# 1_MCU.net
KiCad netlist of a schematic drawn in Altium Designer
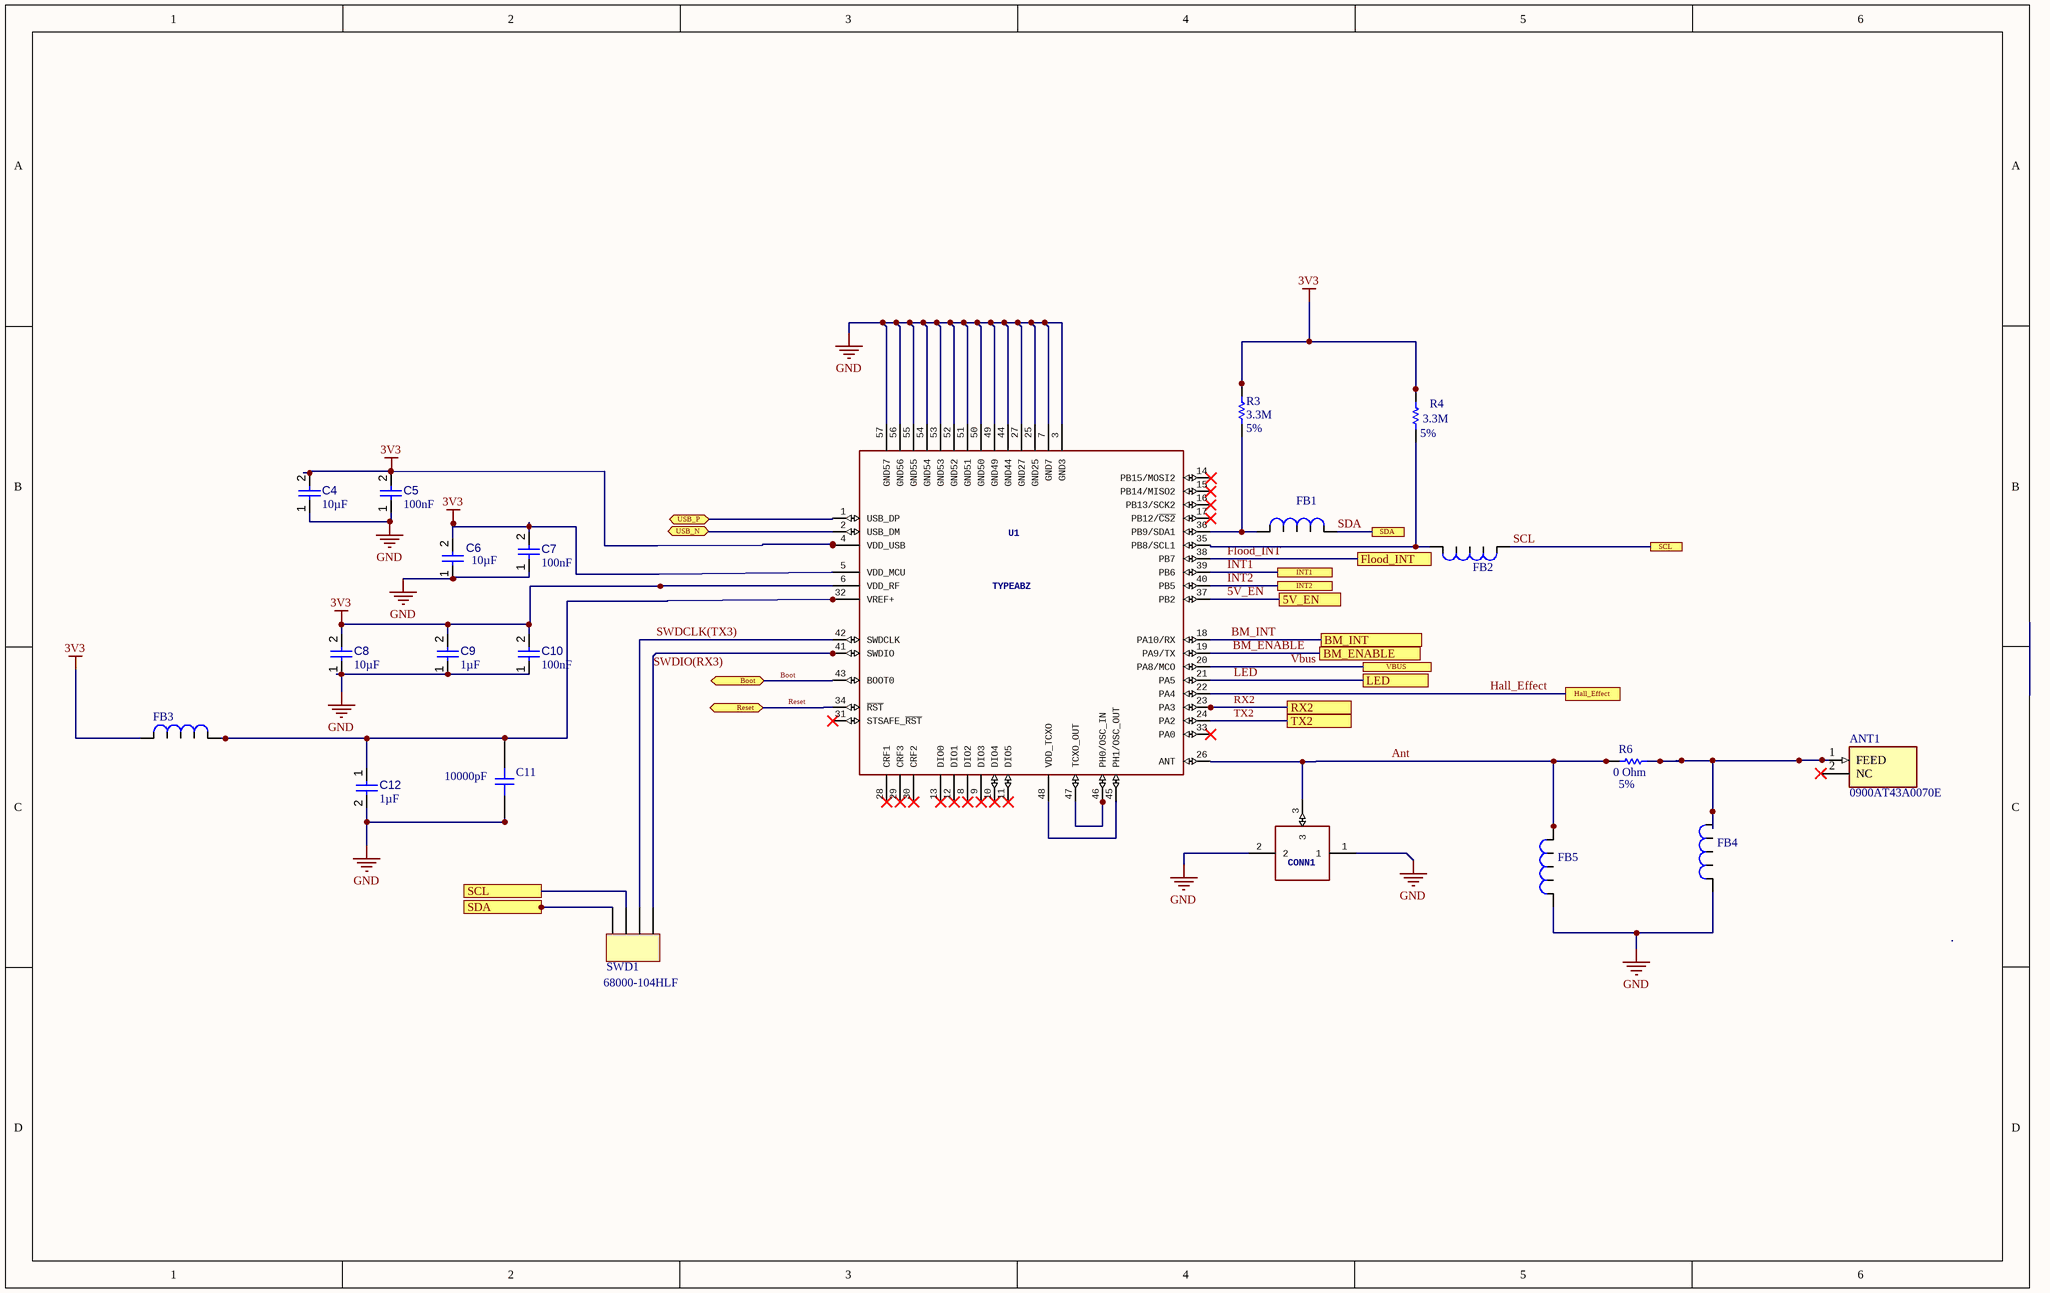
[diagram p0: [1]MCU.SchDoc]

(export (version "E")
  (design (tool "Eeschema 10.0.6"))
  (components
    (comp (ref "ANT1")
      (value "0900AT43A0070E")
      (footprint "SamacSys:ANTC7020X90N")
      (description "Antenna")
      (libsource (lib "Schlib_For_High_Voltage_Sensor") (part "0900AT43A0070E"))
    )
    (comp (ref "C4")
      (value "10µF")
      (footprint "CAPC0603(1608)100_L")
      (description "Chip Capacitor, 10µF +/-20%, 10V, 0603, Thickness 1 mm")
      (fields (field (name "TOLERANCE") "10%") (field (name "Comment") "Capacitor 10µF +/-20% 10V 0603"))
      (libsource (lib "Latium Technologies") (part "CAP-NP-2"))
    )
    (comp (ref "C5")
      (value "100nF")
      (footprint "CAPC1608X90X40ML10T20")
      (description "Chip Capacitor, 100 nF, +/- 10%, 50 V, 0603 (1608 Metric)")
      (fields (field (name "TOLERANCE") "10%") (field (name "Comment") "Capacitor 100 nF +/-10% 50 V 0603"))
      (libsource (lib "Latium Technologies") (part "CAP-NP-2"))
    )
    (comp (ref "C6")
      (value "10µF")
      (footprint "CAPC0603(1608)100_L")
      (description "Chip Capacitor, 10µF +/-20%, 10V, 0603, Thickness 1 mm")
      (fields (field (name "TOLERANCE") "10%") (field (name "Comment") "Capacitor 10µF +/-20% 10V 0603"))
      (libsource (lib "Latium Technologies") (part "CAP-NP-2"))
    )
    (comp (ref "C7")
      (value "100nF")
      (footprint "CAPC1608X90X40ML10T20")
      (description "Chip Capacitor, 100 nF, +/- 10%, 50 V, 0603 (1608 Metric)")
      (fields (field (name "TOLERANCE") "10%") (field (name "Comment") "Capacitor 100 nF +/-10% 50 V 0603"))
      (libsource (lib "Latium Technologies") (part "CAP-NP-2"))
    )
    (comp (ref "C8")
      (value "10µF")
      (footprint "CAPC0603(1608)100_L")
      (description "Chip Capacitor, 10µF +/-20%, 10V, 0603, Thickness 1 mm")
      (fields (field (name "TOLERANCE") "10%") (field (name "Comment") "Capacitor 10µF +/-20% 10V 0603"))
      (libsource (lib "Latium Technologies") (part "CAP-NP-2"))
    )
    (comp (ref "C9")
      (value "1µF")
      (footprint "CAPC1608X90X40ML10T20")
      (description "Chip Capacitor, 1 uF, +/- 10%, 25 V, 0603 (1608 Metric)")
      (fields (field (name "TOLERANCE") "10%") (field (name "Comment") "Capacitor 1 uF +/- 10% 25 V 0603"))
      (libsource (lib "Latium Technologies") (part "CAP-NP-2"))
    )
    (comp (ref "C10")
      (value "100nF")
      (footprint "CAPC1608X90X40ML10T20")
      (description "Chip Capacitor, 100 nF, +/- 10%, 50 V, 0603 (1608 Metric)")
      (fields (field (name "TOLERANCE") "10%") (field (name "Comment") "Capacitor 100 nF +/-10% 50 V 0603"))
      (libsource (lib "Latium Technologies") (part "CAP-NP-2"))
    )
    (comp (ref "C11")
      (value "10000PF")
      (footprint "CAPC0603")
      (description "CAP CER 10000PF 50V X7R 0603")
      (fields
        (field (name "MANUFACTURER") "Murata Electronics North America")
        (field (name "MANUFACTURER PART NUMBER") "GRM188R71H103KA01D")
        (field (name "CAPACITANCE") "10000pF")
      )
      (libsource (lib "Schlib_For_High_Voltage_Sensor") (part "GRM188R71H103KA01D"))
    )
    (comp (ref "C12")
      (value "1µF")
      (footprint "CAPC1608X90X40ML10T20")
      (description "Chip Capacitor, 1 uF, +/- 10%, 25 V, 0603 (1608 Metric)")
      (fields (field (name "TOLERANCE") "10%") (field (name "Comment") "Capacitor 1 uF +/- 10% 25 V 0603"))
      (libsource (lib "Latium Technologies") (part "CAP-NP-2"))
    )
    (comp (ref "CONN1")
      (value "U.FL-R-SMT-1")
      (footprint "U.FL-R-SMT-1")
      (fields (field (name "LIBRARYNAME") "Kris"))
      (libsource (lib "Schlib_For_High_Voltage_Sensor") (part "U.FL-R-SMT-1"))
    )
    (comp (ref "FB1")
      (value "BLM18AG102SN1D")
      (footprint "Ferrite Bead")
      (description "Ferrite Bead 1KOhm @100MHz")
      (libsource (lib "") (part "Ferrite Bead_1"))
    )
    (comp (ref "FB2")
      (value "BLM18AG102SN1D")
      (footprint "Ferrite Bead")
      (description "Ferrite Bead 1KOhm @100MHz")
      (libsource (lib "MasterLib") (part "Ferrite Bead"))
    )
    (comp (ref "FB3")
      (value "BLM18AG102SN1D")
      (footprint "Ferrite Bead")
      (description "Ferrite Bead 1KOhm @100MHz")
      (libsource (lib "MasterLib") (part "Ferrite Bead"))
    )
    (comp (ref "FB4")
      (value "BLM18AG102SN1D")
      (footprint "Ferrite Bead")
      (description "Ferrite Bead 1KOhm @100MHz")
      (libsource (lib "MasterLib") (part "Ferrite Bead"))
    )
    (comp (ref "FB5")
      (value "BLM18AG102SN1D")
      (footprint "Ferrite Bead")
      (description "Ferrite Bead 1KOhm @100MHz")
      (libsource (lib "MasterLib") (part "Ferrite Bead"))
    )
    (comp (ref "R3")
      (value "3.3M")
      (footprint "RES 0603")
      (description "RES 3.3M 5% 0.1W [0603]")
      (fields (field (name "TOLERANCE") "5%"))
      (libsource (lib "MasterLib") (part "RES 3.3M 1% 0.1W [0603]"))
    )
    (comp (ref "R4")
      (value "3.3M")
      (footprint "RES 0603")
      (description "RES 3.3M 5% 0.1W [0603]")
      (fields (field (name "TOLERANCE") "5%"))
      (libsource (lib "MasterLib") (part "RES 3.3M 1% 0.1W [0603]"))
    )
    (comp (ref "R6")
      (value "0 Ohm")
      (footprint "RES 0603")
      (description "RES 0 Ohm 5% 0.1W [0603]")
      (fields (field (name "TOLERANCE") "5%"))
      (libsource (lib "MasterLib") (part "RES 0 Ohm [0603]"))
    )
    (comp (ref "SWD1")
      (value "68000-104HLF")
      (footprint "4POS_HEADER")
      (description "4 Positions Header, Unshrouded Connector 0.100\" (2.54mm) Through Hole Gold or Gold, GXT™")
      (libsource (lib "OTX_Lib_Charger") (part "68000-104HLF"))
    )
    (comp (ref "U1")
      (value "TYPEABZ")
      (footprint "CMWX1ZZABZ")
      (description "CMWX1ZZABZ-078")
      (libsource (lib "Schlib_For_High_Voltage_Sensor") (part "TYPEABZ"))
    )
  )
  (nets
    (net (code "1") (name "/5V_EN") (class "Default")
      (node (ref "U1") (pin "37") (pinfunction "PB2_37") (pintype "bidirectional"))
    )
    (net (code "3") (name "/Ant") (class "Default")
      (node (ref "CONN1") (pin "3") (pinfunction "3_3") (pintype "bidirectional"))
      (node (ref "FB5") (pin "1") (pinfunction "1_1") (pintype "passive"))
      (node (ref "R6") (pin "1") (pinfunction "1_1") (pintype "passive"))
      (node (ref "U1") (pin "26") (pinfunction "ANT_26") (pintype "bidirectional"))
    )
    (net (code "4") (name "/BM_ENABLE") (class "Default")
      (node (ref "U1") (pin "19") (pinfunction "PA9/TX_19") (pintype "bidirectional"))
    )
    (net (code "5") (name "/BM_INT") (class "Default")
      (node (ref "U1") (pin "18") (pinfunction "PA10/RX_18") (pintype "bidirectional"))
    )
    (net (code "6") (name "/Boot") (class "Default")
      (node (ref "U1") (pin "43") (pinfunction "BOOT0_43") (pintype "bidirectional"))
    )
    (net (code "7") (name "/Flood_INT") (class "Default")
      (node (ref "U1") (pin "38") (pinfunction "PB7_38") (pintype "bidirectional"))
    )
    (net (code "8") (name "/Hall_Effect") (class "Default")
      (node (ref "U1") (pin "22") (pinfunction "PA4_22") (pintype "bidirectional"))
    )
    (net (code "9") (name "/INT1") (class "Default")
      (node (ref "U1") (pin "39") (pinfunction "PB6_39") (pintype "bidirectional"))
    )
    (net (code "10") (name "/INT2") (class "Default")
      (node (ref "U1") (pin "40") (pinfunction "PB5_40") (pintype "bidirectional"))
    )
    (net (code "11") (name "/LED") (class "Default")
      (node (ref "U1") (pin "21") (pinfunction "PA5_21") (pintype "bidirectional"))
    )
    (net (code "12") (name "/RX2") (class "Default")
      (node (ref "U1") (pin "23") (pinfunction "PA3_23") (pintype "bidirectional"))
    )
    (net (code "13") (name "/Reset") (class "Default")
      (node (ref "U1") (pin "34") (pinfunction "~{RST}_34") (pintype "bidirectional"))
    )
    (net (code "14") (name "/SCL") (class "Default")
      (node (ref "FB2") (pin "2") (pinfunction "2_2") (pintype "passive"))
      (node (ref "SWD1") (pin "2") (pinfunction "2_2") (pintype "passive"))
    )
    (net (code "15") (name "/SDA") (class "Default")
      (node (ref "FB1") (pin "2") (pinfunction "2_2") (pintype "passive"))
      (node (ref "SWD1") (pin "1") (pinfunction "1_1") (pintype "passive"))
    )
    (net (code "16") (name "/SWDCLK(TX3)") (class "Default")
      (node (ref "SWD1") (pin "3") (pinfunction "3_3") (pintype "passive"))
      (node (ref "U1") (pin "42") (pinfunction "SWDCLK_42") (pintype "bidirectional"))
    )
    (net (code "17") (name "/SWDIO(RX3)") (class "Default")
      (node (ref "SWD1") (pin "4") (pinfunction "3_4") (pintype "passive"))
      (node (ref "U1") (pin "41") (pinfunction "SWDIO_41") (pintype "bidirectional"))
    )
    (net (code "18") (name "/TX2") (class "Default")
      (node (ref "U1") (pin "24") (pinfunction "PA2_24") (pintype "bidirectional"))
    )
    (net (code "19") (name "/USB_N") (class "Default")
      (node (ref "U1") (pin "2") (pinfunction "USB_DM_2") (pintype "bidirectional"))
    )
    (net (code "20") (name "/USB_P") (class "Default")
      (node (ref "U1") (pin "1") (pinfunction "USB_DP_1") (pintype "bidirectional"))
    )
    (net (code "21") (name "/Vbus") (class "Default")
      (node (ref "U1") (pin "20") (pinfunction "PA8/MCO_20") (pintype "bidirectional"))
    )
    (net (code "22") (name "3V3") (class "Default")
      (node (ref "C10") (pin "2") (pinfunction "2_2") (pintype "passive"))
      (node (ref "C4") (pin "2") (pinfunction "2_2") (pintype "passive"))
      (node (ref "C5") (pin "2") (pinfunction "2_2") (pintype "passive"))
      (node (ref "C6") (pin "2") (pinfunction "2_2") (pintype "passive"))
      (node (ref "C7") (pin "2") (pinfunction "2_2") (pintype "passive"))
      (node (ref "C8") (pin "2") (pinfunction "2_2") (pintype "passive"))
      (node (ref "C9") (pin "2") (pinfunction "2_2") (pintype "passive"))
      (node (ref "FB3") (pin "2") (pinfunction "2_2") (pintype "passive"))
      (node (ref "R3") (pin "2") (pinfunction "2_2") (pintype "passive"))
      (node (ref "R4") (pin "2") (pinfunction "2_2") (pintype "passive"))
      (node (ref "U1") (pin "4") (pinfunction "VDD_USB_4") (pintype "power_in"))
      (node (ref "U1") (pin "5") (pinfunction "VDD_MCU_5") (pintype "power_in"))
      (node (ref "U1") (pin "6") (pinfunction "VDD_RF_6") (pintype "power_in"))
    )
    (net (code "23") (name "GND") (class "Default")
      (node (ref "C10") (pin "1") (pinfunction "1_1") (pintype "passive"))
      (node (ref "C11") (pin "1") (pinfunction "1_1") (pintype "passive"))
      (node (ref "C12") (pin "2") (pinfunction "2_2") (pintype "passive"))
      (node (ref "C4") (pin "1") (pinfunction "1_1") (pintype "passive"))
      (node (ref "C5") (pin "1") (pinfunction "1_1") (pintype "passive"))
      (node (ref "C6") (pin "1") (pinfunction "1_1") (pintype "passive"))
      (node (ref "C7") (pin "1") (pinfunction "1_1") (pintype "passive"))
      (node (ref "C8") (pin "1") (pinfunction "1_1") (pintype "passive"))
      (node (ref "C9") (pin "1") (pinfunction "1_1") (pintype "passive"))
      (node (ref "CONN1") (pin "1") (pinfunction "1_1") (pintype "power_in"))
      (node (ref "CONN1") (pin "2") (pinfunction "2_2") (pintype "power_in"))
      (node (ref "FB4") (pin "2") (pinfunction "2_2") (pintype "passive"))
      (node (ref "FB5") (pin "2") (pinfunction "2_2") (pintype "passive"))
      (node (ref "U1") (pin "25") (pinfunction "GND25_25") (pintype "power_in"))
      (node (ref "U1") (pin "27") (pinfunction "GND27_27") (pintype "power_in"))
      (node (ref "U1") (pin "3") (pinfunction "GND3_3") (pintype "power_in"))
      (node (ref "U1") (pin "44") (pinfunction "GND44_44") (pintype "power_in"))
      (node (ref "U1") (pin "49") (pinfunction "GND49_49") (pintype "power_in"))
      (node (ref "U1") (pin "50") (pinfunction "GND50_50") (pintype "power_in"))
      (node (ref "U1") (pin "51") (pinfunction "GND51_51") (pintype "power_in"))
      (node (ref "U1") (pin "52") (pinfunction "GND52_52") (pintype "power_in"))
      (node (ref "U1") (pin "53") (pinfunction "GND53_53") (pintype "power_in"))
      (node (ref "U1") (pin "54") (pinfunction "GND54_54") (pintype "power_in"))
      (node (ref "U1") (pin "55") (pinfunction "GND55_55") (pintype "power_in"))
      (node (ref "U1") (pin "56") (pinfunction "GND56_56") (pintype "power_in"))
      (node (ref "U1") (pin "57") (pinfunction "GND57_57") (pintype "power_in"))
      (node (ref "U1") (pin "7") (pinfunction "GND7_7") (pintype "power_in"))
    )
    (net (code "24") (name "Net-(ANT1-FEED)") (class "Default")
      (node (ref "ANT1") (pin "1") (pinfunction "FEED_1") (pintype "input"))
      (node (ref "FB4") (pin "1") (pinfunction "1_1") (pintype "passive"))
      (node (ref "R6") (pin "2") (pinfunction "2_2") (pintype "passive"))
    )
    (net (code "25") (name "Net-(U1-PB8{slash}SCL1)") (class "Default")
      (node (ref "FB2") (pin "1") (pinfunction "1_1") (pintype "passive"))
      (node (ref "R4") (pin "1") (pinfunction "1_1") (pintype "passive"))
      (node (ref "U1") (pin "35") (pinfunction "PB8/SCL1_35") (pintype "bidirectional"))
    )
    (net (code "26") (name "Net-(U1-PB9{slash}SDA1)") (class "Default")
      (node (ref "FB1") (pin "1") (pinfunction "1_1") (pintype "passive"))
      (node (ref "R3") (pin "1") (pinfunction "1_1") (pintype "passive"))
      (node (ref "U1") (pin "36") (pinfunction "PB9/SDA1_36") (pintype "bidirectional"))
    )
    (net (code "27") (name "Net-(U1-PH0{slash}OSC_IN)") (class "Default")
      (node (ref "U1") (pin "46") (pinfunction "PH0/OSC_IN_46") (pintype "bidirectional"))
      (node (ref "U1") (pin "47") (pinfunction "TCXO_OUT_47") (pintype "bidirectional"))
    )
    (net (code "28") (name "Net-(U1-PH1{slash}OSC_OUT)") (class "Default")
      (node (ref "U1") (pin "45") (pinfunction "PH1/OSC_OUT_45") (pintype "bidirectional"))
      (node (ref "U1") (pin "48") (pinfunction "VDD_TCXO_48") (pintype "power_in"))
    )
    (net (code "29") (name "Net-(U1-VREF+)") (class "Default")
      (node (ref "C11") (pin "2") (pinfunction "2_2") (pintype "passive"))
      (node (ref "C12") (pin "1") (pinfunction "1_1") (pintype "passive"))
      (node (ref "FB3") (pin "1") (pinfunction "1_1") (pintype "passive"))
      (node (ref "U1") (pin "32") (pinfunction "VREF+_32") (pintype "power_in"))
    )
    (net (code "30") (name "unconnected-(ANT1-NC-Pad2)") (class "Default")
      (node (ref "ANT1") (pin "2") (pinfunction "NC_2") (pintype "passive"))
    )
    (net (code "31") (name "unconnected-(U1-CRF1-Pad28)") (class "Default")
      (node (ref "U1") (pin "28") (pinfunction "CRF1_28") (pintype "passive+no_connect"))
    )
    (net (code "32") (name "unconnected-(U1-CRF2-Pad30)") (class "Default")
      (node (ref "U1") (pin "30") (pinfunction "CRF2_30") (pintype "passive+no_connect"))
    )
    (net (code "33") (name "unconnected-(U1-CRF3-Pad29)") (class "Default")
      (node (ref "U1") (pin "29") (pinfunction "CRF3_29") (pintype "passive+no_connect"))
    )
    (net (code "34") (name "unconnected-(U1-DIO0-Pad13)") (class "Default")
      (node (ref "U1") (pin "13") (pinfunction "DIO0_13") (pintype "passive+no_connect"))
    )
    (net (code "35") (name "unconnected-(U1-DIO1-Pad12)") (class "Default")
      (node (ref "U1") (pin "12") (pinfunction "DIO1_12") (pintype "passive+no_connect"))
    )
    (net (code "36") (name "unconnected-(U1-DIO2-Pad8)") (class "Default")
      (node (ref "U1") (pin "8") (pinfunction "DIO2_8") (pintype "passive+no_connect"))
    )
    (net (code "37") (name "unconnected-(U1-DIO3-Pad9)") (class "Default")
      (node (ref "U1") (pin "9") (pinfunction "DIO3_9") (pintype "passive+no_connect"))
    )
    (net (code "38") (name "unconnected-(U1-DIO4-Pad10)") (class "Default")
      (node (ref "U1") (pin "10") (pinfunction "DIO4_10") (pintype "bidirectional+no_connect"))
    )
    (net (code "39") (name "unconnected-(U1-DIO5-Pad11)") (class "Default")
      (node (ref "U1") (pin "11") (pinfunction "DIO5_11") (pintype "bidirectional+no_connect"))
    )
    (net (code "40") (name "unconnected-(U1-PA0-Pad33)") (class "Default")
      (node (ref "U1") (pin "33") (pinfunction "PA0_33") (pintype "bidirectional+no_connect"))
    )
    (net (code "41") (name "unconnected-(U1-PB12{slash}~{CS2}-Pad17)") (class "Default")
      (node (ref "U1") (pin "17") (pinfunction "PB12/~{CS2}_17") (pintype "bidirectional+no_connect"))
    )
    (net (code "42") (name "unconnected-(U1-PB13{slash}SCK2-Pad16)") (class "Default")
      (node (ref "U1") (pin "16") (pinfunction "PB13/SCK2_16") (pintype "bidirectional+no_connect"))
    )
    (net (code "43") (name "unconnected-(U1-PB14{slash}MISO2-Pad15)") (class "Default")
      (node (ref "U1") (pin "15") (pinfunction "PB14/MISO2_15") (pintype "bidirectional+no_connect"))
    )
    (net (code "44") (name "unconnected-(U1-PB15{slash}MOSI2-Pad14)") (class "Default")
      (node (ref "U1") (pin "14") (pinfunction "PB15/MOSI2_14") (pintype "bidirectional"))
    )
    (net (code "45") (name "unconnected-(U1-STSAFE_~{RST}-Pad31)") (class "Default")
      (node (ref "U1") (pin "31") (pinfunction "STSAFE_~{RST}_31") (pintype "bidirectional+no_connect"))
    )
  )
)
